# Qwiic_Shield_for_Thing_Plus.net
KiCad netlist of a schematic drawn in EAGLE
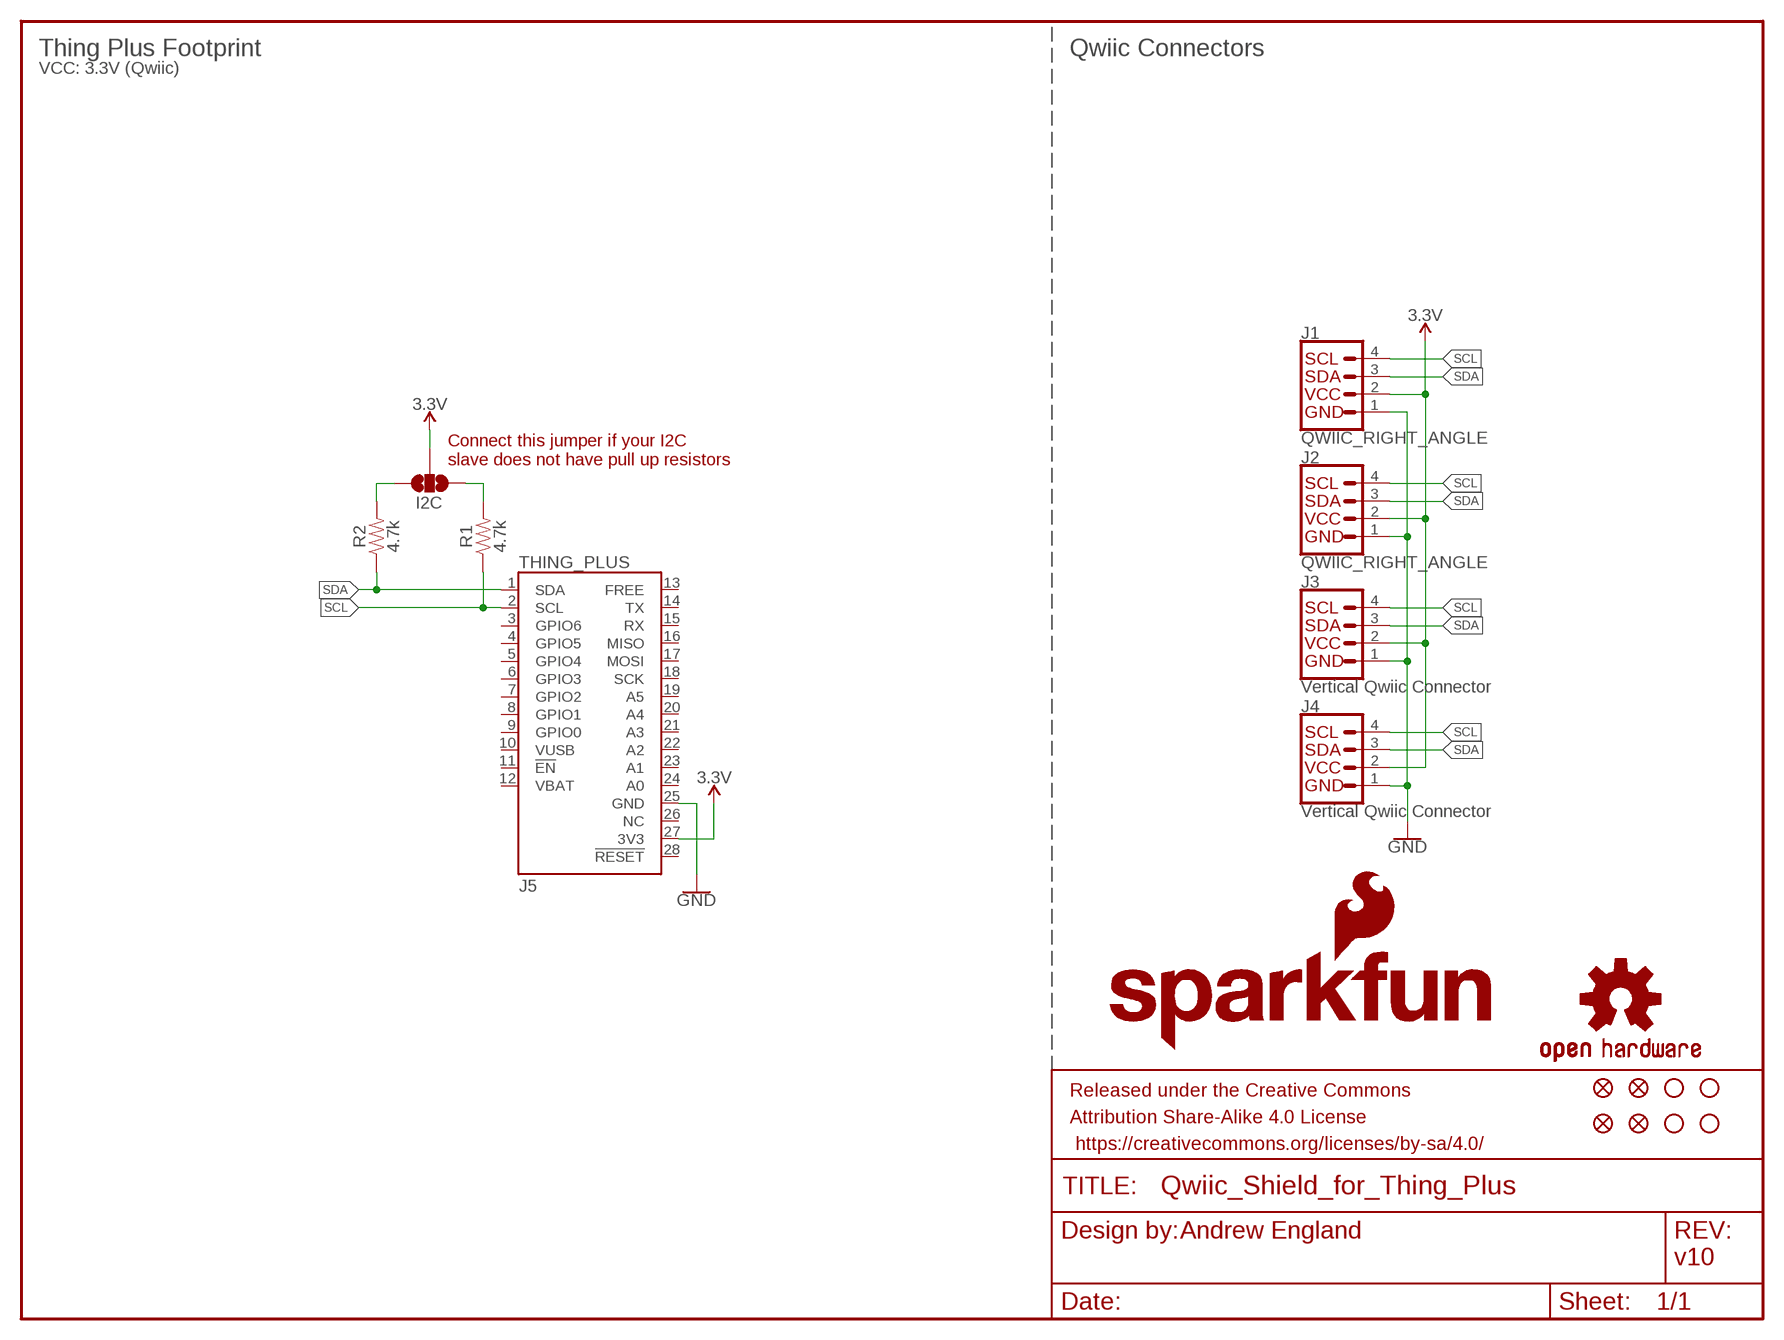
[diagram p0: schematic, sheet 1]

(export (version "E")
  (design (tool "Eeschema 10.0.6"))
  (components
    (comp (ref "FD1")
      (value "FIDUCIAL1X2")
      (footprint "eagle-import:FIDUCIAL-1X2")
      (libsource (lib "eagle-import") (part "FIDUCIAL1X2"))
    )
    (comp (ref "FD2")
      (value "FIDUCIAL1X2")
      (footprint "eagle-import:FIDUCIAL-1X2")
      (libsource (lib "eagle-import") (part "FIDUCIAL1X2"))
    )
    (comp (ref "FD3")
      (value "FIDUCIAL1X2")
      (footprint "eagle-import:FIDUCIAL-1X2")
      (libsource (lib "eagle-import") (part "FIDUCIAL1X2"))
    )
    (comp (ref "FD4")
      (value "FIDUCIAL1X2")
      (footprint "eagle-import:FIDUCIAL-1X2")
      (libsource (lib "eagle-import") (part "FIDUCIAL1X2"))
    )
    (comp (ref "FRAME1")
      (value "FRAME-LETTER")
      (footprint "eagle-import:CREATIVE_COMMONS")
      (libsource (lib "eagle-import") (part "FRAME-LETTER"))
    )
    (comp (ref "H1")
      (value "STAND-OFF")
      (footprint "eagle-import:STAND-OFF")
      (libsource (lib "eagle-import") (part "STAND-OFF"))
    )
    (comp (ref "H2")
      (value "STAND-OFF")
      (footprint "eagle-import:STAND-OFF")
      (libsource (lib "eagle-import") (part "STAND-OFF"))
    )
    (comp (ref "H3")
      (value "STAND-OFF")
      (footprint "eagle-import:STAND-OFF")
      (libsource (lib "eagle-import") (part "STAND-OFF"))
    )
    (comp (ref "H4")
      (value "STAND-OFF")
      (footprint "eagle-import:STAND-OFF")
      (libsource (lib "eagle-import") (part "STAND-OFF"))
    )
    (comp (ref "I2C")
      (value "JUMPER-SMT_3_NO_NO-SILK")
      (footprint "eagle-import:SMT-JUMPER_3_NO_NO-SILK")
      (libsource (lib "eagle-import") (part "JUMPER-SMT_3_NO_NO-SILK"))
    )
    (comp (ref "J1")
      (value "QWIIC_RIGHT_ANGLE")
      (footprint "eagle-import:JST04_1MM_RA")
      (libsource (lib "eagle-import") (part "QWIIC_CONNECTORJS-1MM"))
    )
    (comp (ref "J2")
      (value "QWIIC_RIGHT_ANGLE")
      (footprint "eagle-import:JST04_1MM_RA")
      (libsource (lib "eagle-import") (part "QWIIC_CONNECTORJS-1MM"))
    )
    (comp (ref "J3")
      (value "Vertical Qwiic Connector")
      (footprint "eagle-import:JST04_1MM_VERT")
      (libsource (lib "eagle-import") (part "QWIIC_CONNECTOR"))
    )
    (comp (ref "J4")
      (value "Vertical Qwiic Connector")
      (footprint "eagle-import:JST04_1MM_VERT")
      (libsource (lib "eagle-import") (part "QWIIC_CONNECTOR"))
    )
    (comp (ref "J5")
      (value "THING_PLUS")
      (footprint "eagle-import:THING_PLUS")
      (libsource (lib "eagle-import") (part "THING_PLUS"))
    )
    (comp (ref "LOGO1")
      (value "SFE_LOGO_NAME_FLAME.1_INCH")
      (footprint "eagle-import:SFE_LOGO_NAME_FLAME_.1")
      (libsource (lib "eagle-import") (part "SFE_LOGO_NAME_FLAME.1_INCH"))
    )
    (comp (ref "LOGO2")
      (value "SFE_LOGO_NAME_FLAME.2_INCH")
      (footprint "eagle-import:SFE_LOGO_NAME_FLAME_.2")
      (libsource (lib "eagle-import") (part "SFE_LOGO_NAME_FLAME.2_INCH"))
    )
    (comp (ref "LOGO3")
      (value "OSHW-LOGOS")
      (footprint "eagle-import:OSHW-LOGO-S")
      (libsource (lib "eagle-import") (part "OSHW-LOGOS"))
    )
    (comp (ref "R1")
      (value "4.7k")
      (footprint "eagle-import:0603")
      (libsource (lib "eagle-import") (part "4.7KOHM-0603-1/10W-1%"))
    )
    (comp (ref "R2")
      (value "4.7k")
      (footprint "eagle-import:0603")
      (libsource (lib "eagle-import") (part "4.7KOHM-0603-1/10W-1%"))
    )
  )
  (nets
    (net (code "1") (name "3.3V") (class "Default")
      (node (ref "I2C") (pin "2") (pinfunction "2_2") (pintype "passive"))
      (node (ref "J1") (pin "2") (pinfunction "2_2") (pintype "power_in"))
      (node (ref "J2") (pin "2") (pinfunction "2_2") (pintype "power_in"))
      (node (ref "J3") (pin "2") (pinfunction "2_2") (pintype "power_in"))
      (node (ref "J4") (pin "2") (pinfunction "2_2") (pintype "power_in"))
      (node (ref "J5") (pin "27") (pinfunction "3V3_27") (pintype "bidirectional"))
    )
    (net (code "2") (name "GND") (class "Default")
      (node (ref "J1") (pin "1") (pinfunction "1_1") (pintype "power_in"))
      (node (ref "J2") (pin "1") (pinfunction "1_1") (pintype "power_in"))
      (node (ref "J3") (pin "1") (pinfunction "1_1") (pintype "power_in"))
      (node (ref "J4") (pin "1") (pinfunction "1_1") (pintype "power_in"))
      (node (ref "J5") (pin "25") (pinfunction "GND_25") (pintype "bidirectional"))
    )
    (net (code "3") (name "Net-(I2C-Pad1)") (class "Default")
      (node (ref "I2C") (pin "1") (pinfunction "1_1") (pintype "passive"))
      (node (ref "R1") (pin "2") (pinfunction "2_2") (pintype "passive"))
    )
    (net (code "4") (name "Net-(I2C-Pad3)") (class "Default")
      (node (ref "I2C") (pin "3") (pinfunction "3_3") (pintype "passive"))
      (node (ref "R2") (pin "2") (pinfunction "2_2") (pintype "passive"))
    )
    (net (code "5") (name "SCL") (class "Default")
      (node (ref "J1") (pin "4") (pinfunction "4_4") (pintype "passive"))
      (node (ref "J2") (pin "4") (pinfunction "4_4") (pintype "passive"))
      (node (ref "J3") (pin "4") (pinfunction "4_4") (pintype "passive"))
      (node (ref "J4") (pin "4") (pinfunction "4_4") (pintype "passive"))
      (node (ref "J5") (pin "2") (pinfunction "SCL_2") (pintype "bidirectional"))
      (node (ref "R1") (pin "1") (pinfunction "1_1") (pintype "passive"))
    )
    (net (code "6") (name "SDA") (class "Default")
      (node (ref "J1") (pin "3") (pinfunction "3_3") (pintype "passive"))
      (node (ref "J2") (pin "3") (pinfunction "3_3") (pintype "passive"))
      (node (ref "J3") (pin "3") (pinfunction "3_3") (pintype "passive"))
      (node (ref "J4") (pin "3") (pinfunction "3_3") (pintype "passive"))
      (node (ref "J5") (pin "1") (pinfunction "SDA_1") (pintype "bidirectional"))
      (node (ref "R2") (pin "1") (pinfunction "1_1") (pintype "passive"))
    )
    (net (code "7") (name "unconnected-(J5-A0-Pad24)") (class "Default")
      (node (ref "J5") (pin "24") (pinfunction "A0_24") (pintype "bidirectional"))
    )
    (net (code "8") (name "unconnected-(J5-A1-Pad23)") (class "Default")
      (node (ref "J5") (pin "23") (pinfunction "A1_23") (pintype "bidirectional"))
    )
    (net (code "9") (name "unconnected-(J5-A2-Pad22)") (class "Default")
      (node (ref "J5") (pin "22") (pinfunction "A2_22") (pintype "bidirectional"))
    )
    (net (code "10") (name "unconnected-(J5-A3-Pad21)") (class "Default")
      (node (ref "J5") (pin "21") (pinfunction "A3_21") (pintype "bidirectional"))
    )
    (net (code "11") (name "unconnected-(J5-A4-Pad20)") (class "Default")
      (node (ref "J5") (pin "20") (pinfunction "A4_20") (pintype "bidirectional"))
    )
    (net (code "12") (name "unconnected-(J5-A5-Pad19)") (class "Default")
      (node (ref "J5") (pin "19") (pinfunction "A5_19") (pintype "bidirectional"))
    )
    (net (code "13") (name "unconnected-(J5-FREE-Pad13)") (class "Default")
      (node (ref "J5") (pin "13") (pinfunction "FREE_13") (pintype "bidirectional"))
    )
    (net (code "14") (name "unconnected-(J5-GPIO0-Pad9)") (class "Default")
      (node (ref "J5") (pin "9") (pinfunction "GPIO0_9") (pintype "bidirectional"))
    )
    (net (code "15") (name "unconnected-(J5-GPIO1-Pad8)") (class "Default")
      (node (ref "J5") (pin "8") (pinfunction "GPIO1_8") (pintype "bidirectional"))
    )
    (net (code "16") (name "unconnected-(J5-GPIO2-Pad7)") (class "Default")
      (node (ref "J5") (pin "7") (pinfunction "GPIO2_7") (pintype "bidirectional"))
    )
    (net (code "17") (name "unconnected-(J5-GPIO3-Pad6)") (class "Default")
      (node (ref "J5") (pin "6") (pinfunction "GPIO3_6") (pintype "bidirectional"))
    )
    (net (code "18") (name "unconnected-(J5-GPIO4-Pad5)") (class "Default")
      (node (ref "J5") (pin "5") (pinfunction "GPIO4_5") (pintype "bidirectional"))
    )
    (net (code "19") (name "unconnected-(J5-GPIO5-Pad4)") (class "Default")
      (node (ref "J5") (pin "4") (pinfunction "GPIO5_4") (pintype "bidirectional"))
    )
    (net (code "20") (name "unconnected-(J5-GPIO6-Pad3)") (class "Default")
      (node (ref "J5") (pin "3") (pinfunction "GPIO6_3") (pintype "bidirectional"))
    )
    (net (code "21") (name "unconnected-(J5-MISO-Pad16)") (class "Default")
      (node (ref "J5") (pin "16") (pinfunction "MISO_16") (pintype "bidirectional"))
    )
    (net (code "22") (name "unconnected-(J5-MOSI-Pad17)") (class "Default")
      (node (ref "J5") (pin "17") (pinfunction "MOSI_17") (pintype "bidirectional"))
    )
    (net (code "23") (name "unconnected-(J5-NC-Pad26)") (class "Default")
      (node (ref "J5") (pin "26") (pinfunction "NC_26") (pintype "bidirectional"))
    )
    (net (code "24") (name "unconnected-(J5-RX-Pad15)") (class "Default")
      (node (ref "J5") (pin "15") (pinfunction "RX_15") (pintype "bidirectional"))
    )
    (net (code "25") (name "unconnected-(J5-SCK-Pad18)") (class "Default")
      (node (ref "J5") (pin "18") (pinfunction "SCK_18") (pintype "bidirectional"))
    )
    (net (code "26") (name "unconnected-(J5-TX-Pad14)") (class "Default")
      (node (ref "J5") (pin "14") (pinfunction "TX_14") (pintype "bidirectional"))
    )
    (net (code "27") (name "unconnected-(J5-VBAT-Pad12)") (class "Default")
      (node (ref "J5") (pin "12") (pinfunction "VBAT_12") (pintype "bidirectional"))
    )
    (net (code "28") (name "unconnected-(J5-VUSB-Pad10)") (class "Default")
      (node (ref "J5") (pin "10") (pinfunction "VUSB_10") (pintype "bidirectional"))
    )
    (net (code "29") (name "unconnected-(J5-~{EN}-Pad11)") (class "Default")
      (node (ref "J5") (pin "11") (pinfunction "~{EN}_11") (pintype "bidirectional"))
    )
    (net (code "30") (name "unconnected-(J5-~{RESET}-Pad28)") (class "Default")
      (node (ref "J5") (pin "28") (pinfunction "~{RESET}_28") (pintype "bidirectional"))
    )
  )
)
